# ESC.net
KiCad netlist of a schematic drawn in Altium Designer
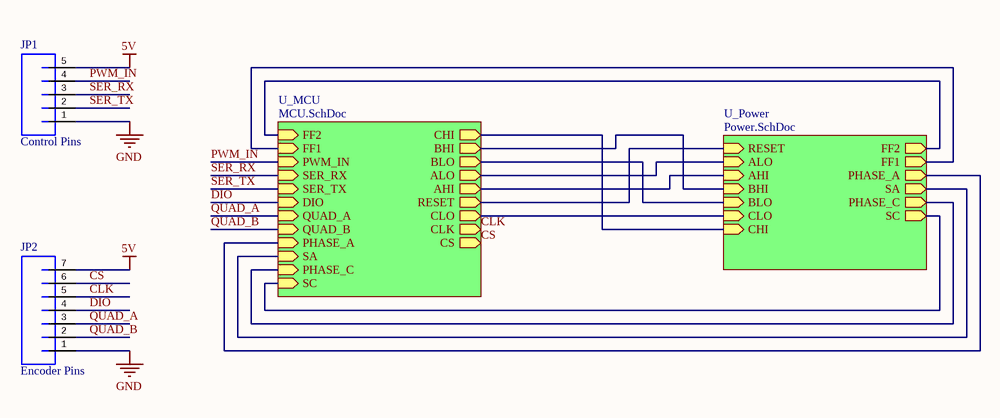
[diagram p0: ESC.SchDoc]

(export (version "E")
  (design (tool "Eeschema 10.0.6"))
  (components
    (comp (ref "JP1")
      (value "Control Pins")
      (footprint "JST-5-PTH-VERT")
      (libsource (lib "Components") (part "JST_5_VERT"))
    )
    (comp (ref "JP2")
      (value "Encoder Pins")
      (footprint "JST-7-PTH-VERT")
      (libsource (lib "Components") (part "JST_7_VERT"))
    )
  )
  (nets
    (net (code "6") (name "/CLK") (class "Default")
      (node (ref "JP2") (pin "5") (pinfunction "5_5") (pintype "passive"))
    )
    (net (code "8") (name "/CS") (class "Default")
      (node (ref "JP2") (pin "6") (pinfunction "6_6") (pintype "passive"))
    )
    (net (code "9") (name "/DIO") (class "Default")
      (node (ref "JP2") (pin "4") (pinfunction "4_4") (pintype "passive"))
    )
    (net (code "14") (name "/PWM_IN") (class "Default")
      (node (ref "JP1") (pin "4") (pinfunction "4_4") (pintype "passive"))
    )
    (net (code "15") (name "/QUAD_A") (class "Default")
      (node (ref "JP2") (pin "3") (pinfunction "3_3") (pintype "passive"))
    )
    (net (code "16") (name "/QUAD_B") (class "Default")
      (node (ref "JP2") (pin "2") (pinfunction "2_2") (pintype "passive"))
    )
    (net (code "20") (name "/SER_RX") (class "Default")
      (node (ref "JP1") (pin "3") (pinfunction "3_3") (pintype "passive"))
    )
    (net (code "21") (name "/SER_TX") (class "Default")
      (node (ref "JP1") (pin "2") (pinfunction "2_2") (pintype "passive"))
    )
    (net (code "22") (name "5V") (class "Default")
      (node (ref "JP1") (pin "5") (pinfunction "5_5") (pintype "passive"))
      (node (ref "JP2") (pin "7") (pinfunction "7_7") (pintype "passive"))
    )
    (net (code "23") (name "GND") (class "Default")
      (node (ref "JP1") (pin "1") (pinfunction "1_1") (pintype "passive"))
      (node (ref "JP2") (pin "1") (pinfunction "1_1") (pintype "passive"))
    )
  )
)
